# Regulador.net
KiCad netlist of a schematic drawn in EAGLE
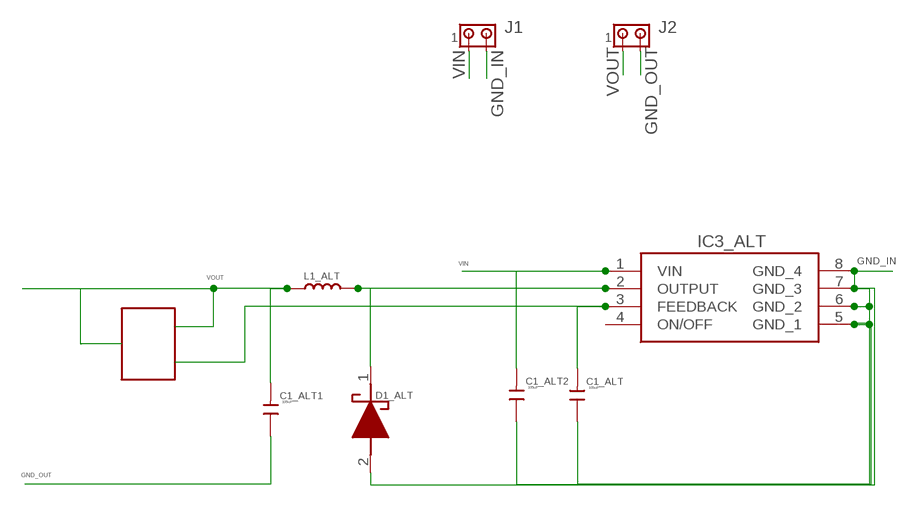
[diagram p0: schematic, sheet 1]

(export (version "E")
  (design (tool "Eeschema 10.0.6"))
  (components
    (comp (ref "C1_ALT")
      (value "105uF")
      (footprint "eagle-import:C0805")
      (libsource (lib "eagle-import") (part "C-0805"))
    )
    (comp (ref "C1_ALT1")
      (value "105uF")
      (footprint "eagle-import:C0805")
      (libsource (lib "eagle-import") (part "C-0805"))
    )
    (comp (ref "C1_ALT2")
      (value "105uF")
      (footprint "eagle-import:C0805")
      (libsource (lib "eagle-import") (part "C-0805"))
    )
    (comp (ref "D1_ALT")
      (value "1N5819HW1-7-F")
      (footprint "eagle-import:SODFL3518X115N")
      (fields (field (name "MOUSER_PART_NUMBER") "621-1N5819HW1-7-F"))
      (libsource (lib "eagle-import") (part "1N5819HW1-7-F"))
    )
    (comp (ref "IC3_ALT")
      (value "XL1509-3.3E1")
      (footprint "eagle-import:SOIC127P600X175-8N")
      (libsource (lib "eagle-import") (part "XL1509-3.3E1"))
    )
    (comp (ref "J1")
      (value "MTA02-156")
      (footprint "eagle-import:1X2MTA")
      (libsource (lib "eagle-import") (part "MTA02-156"))
    )
    (comp (ref "J2")
      (value "MTA02-156")
      (footprint "eagle-import:1X2MTA")
      (libsource (lib "eagle-import") (part "MTA02-156"))
    )
    (comp (ref "L1_ALT")
      (value "47uH")
      (footprint "eagle-import:PIO73")
      (libsource (lib "eagle-import") (part "L'PIO73'"))
    )
    (comp (ref "U$1")
      (value "TRIMPOT")
      (footprint "eagle-import:TRIMPOT")
      (libsource (lib "eagle-import") (part "TRIMPOT"))
    )
  )
  (nets
    (net (code "1") (name "/GND_IN") (class "Default")
      (node (ref "C1_ALT") (pin "1") (pinfunction "1_1") (pintype "passive"))
      (node (ref "C1_ALT2") (pin "1") (pinfunction "1_1") (pintype "passive"))
      (node (ref "D1_ALT") (pin "2") (pinfunction "A_2") (pintype "bidirectional"))
      (node (ref "IC3_ALT") (pin "5") (pinfunction "GND_1_5") (pintype "bidirectional"))
      (node (ref "IC3_ALT") (pin "6") (pinfunction "GND_2_6") (pintype "bidirectional"))
      (node (ref "IC3_ALT") (pin "7") (pinfunction "GND_3_7") (pintype "bidirectional"))
      (node (ref "IC3_ALT") (pin "8") (pinfunction "GND_4_8") (pintype "bidirectional"))
      (node (ref "J1") (pin "2") (pinfunction "2_2") (pintype "passive"))
    )
    (net (code "2") (name "/GND_OUT") (class "Default")
      (node (ref "C1_ALT1") (pin "1") (pinfunction "1_1") (pintype "passive"))
      (node (ref "J2") (pin "2") (pinfunction "2_2") (pintype "passive"))
    )
    (net (code "3") (name "/VIN") (class "Default")
      (node (ref "C1_ALT2") (pin "2") (pinfunction "2_2") (pintype "passive"))
      (node (ref "IC3_ALT") (pin "1") (pinfunction "VIN_1") (pintype "bidirectional"))
      (node (ref "J1") (pin "1") (pinfunction "1_1") (pintype "passive"))
    )
    (net (code "4") (name "/VOUT") (class "Default")
      (node (ref "C1_ALT1") (pin "2") (pinfunction "2_2") (pintype "passive"))
      (node (ref "J2") (pin "1") (pinfunction "1_1") (pintype "passive"))
      (node (ref "L1_ALT") (pin "2") (pinfunction "2_2") (pintype "passive"))
      (node (ref "U$1") (pin "VCC1") (pinfunction "VCC1_VCC1") (pintype "bidirectional"))
      (node (ref "U$1") (pin "VCC2") (pinfunction "VCC2_VCC2") (pintype "bidirectional"))
    )
    (net (code "5") (name "Net-(D1_ALT-K)") (class "Default")
      (node (ref "D1_ALT") (pin "1") (pinfunction "K_1") (pintype "bidirectional"))
      (node (ref "IC3_ALT") (pin "2") (pinfunction "OUTPUT_2") (pintype "bidirectional"))
      (node (ref "L1_ALT") (pin "1") (pinfunction "1_1") (pintype "passive"))
    )
    (net (code "6") (name "Net-(IC3_ALT-FEEDBACK)") (class "Default")
      (node (ref "C1_ALT") (pin "2") (pinfunction "2_2") (pintype "passive"))
      (node (ref "IC3_ALT") (pin "3") (pinfunction "FEEDBACK_3") (pintype "bidirectional"))
      (node (ref "U$1") (pin "OUT") (pinfunction "OUT_OUT") (pintype "bidirectional"))
    )
    (net (code "7") (name "unconnected-(IC3_ALT-ON{slash}OFF-Pad4)") (class "Default")
      (node (ref "IC3_ALT") (pin "4") (pinfunction "ON/OFF_4") (pintype "bidirectional"))
    )
  )
)
